# PowerOut.net
KiCad netlist of a schematic drawn in Altium Designer
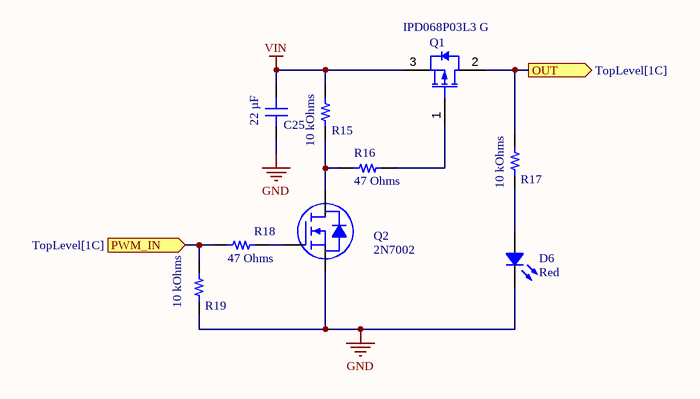
[diagram p0: PowerOut.SchDoc]

(export (version "E")
  (design (tool "Eeschema 10.0.6"))
  (components
    (comp (ref "C25")
      (value "22 µF")
      (footprint "CAP 0805_2012")
      (description "CAP0805 X5R 22UF 20% 35V")
      (fields (field (name "TOLERANCE") "±20%") (field (name "PART NUMBER") "GMC21X5R226M35NT"))
      (libsource (lib "Celestial Altium Library - altium_library") (part "Capacitor"))
    )
    (comp (ref "D6")
      (value "Red")
      (footprint "LED 0603_1608 RED")
      (description "LED RED CLEAR 0603 SMD")
      (fields
        (field (name "PART NUMBER") "LR Q976.01-P2R2-1")
        (field (name "MANUFACTURER") "ams-OSRAM USA Inc.")
      )
      (libsource (lib "Celestial Altium Library - altium_library") (part "LED"))
    )
    (comp (ref "Q1")
      (value "IPD068P03L3 G")
      (footprint "IPD068P03L3_G_0:INF-PG-TO252-3-1_M")
      (fields (field (name "MANUFACTURER") "Infineon"))
      (libsource (lib "IPD068P03L3_G") (part "IPD068P03L3 G"))
    )
    (comp (ref "Q2")
      (value "2N7002")
      (footprint "ON SEMI SOT-23-3")
      (description "MOSFET N-CH 60V 115MA SOT-23")
      (fields (field (name "MANUFACTURER") "ON Semiconductor"))
      (libsource (lib "Celestial Altium Library - altium_library") (part "ON SEMI MOSFET N-CH SOT-23-3"))
    )
    (comp (ref "R15")
      (value "10 kOhms")
      (footprint "YAGEO RES 0603_1608")
      (description "RES SMD 10K OHM 1% 1/10W 0603")
      (fields (field (name "TOLERANCE") "±1%") (field (name "PART NUMBER") "AC0603FR-0710KL"))
      (libsource (lib "Celestial Altium Library - altium_library") (part "Resistor"))
    )
    (comp (ref "R16")
      (value "47 Ohms")
      (footprint "YAGEO RES 0603_1608")
      (description "RES SMD 47 OHM 1% 1/10W 0603")
      (fields (field (name "TOLERANCE") "±1%") (field (name "PART NUMBER") "AC0603FR-0747RL"))
      (libsource (lib "Celestial Altium Library - altium_library") (part "Resistor"))
    )
    (comp (ref "R17")
      (value "10 kOhms")
      (footprint "YAGEO RES 0603_1608")
      (description "RES SMD 10K OHM 1% 1/10W 0603")
      (fields (field (name "TOLERANCE") "±1%") (field (name "PART NUMBER") "RV0603FR-0710KL"))
      (libsource (lib "Celestial Altium Library - altium_library") (part "Resistor"))
    )
    (comp (ref "R18")
      (value "47 Ohms")
      (footprint "YAGEO RES 0603_1608")
      (description "RES 47 OHM 1% 1/10W 0603")
      (fields (field (name "TOLERANCE") "±1%") (field (name "PART NUMBER") "RC0603FR-0747RL"))
      (libsource (lib "Celestial Altium Library - altium_library") (part "Resistor"))
    )
    (comp (ref "R19")
      (value "10 kOhms")
      (footprint "YAGEO RES 0603_1608")
      (description "RES SMD 10K OHM 0.25% 1/10W 0603")
      (fields (field (name "TOLERANCE") "±0.25%") (field (name "PART NUMBER") "RT0603CRE0710KL"))
      (libsource (lib "Celestial Altium Library - altium_library") (part "Resistor"))
    )
  )
  (nets
    (net (code "1") (name "/OUT") (class "Default")
      (node (ref "Q1") (pin "2") (pinfunction "DRAIN_2") (pintype "passive"))
      (node (ref "R17") (pin "1") (pinfunction "1_1") (pintype "passive"))
    )
    (net (code "2") (name "/PWM_IN") (class "Default")
      (node (ref "R18") (pin "1") (pinfunction "1_1") (pintype "passive"))
      (node (ref "R19") (pin "1") (pinfunction "1_1") (pintype "passive"))
    )
    (net (code "3") (name "GND") (class "Default")
      (node (ref "C25") (pin "2") (pinfunction "2_2") (pintype "passive"))
      (node (ref "D6") (pin "2") (pinfunction "2_2") (pintype "passive"))
      (node (ref "Q2") (pin "2") (pinfunction "S_2") (pintype "passive"))
      (node (ref "R19") (pin "2") (pinfunction "2_2") (pintype "passive"))
    )
    (net (code "4") (name "Net-(D6-Pad1)") (class "Default")
      (node (ref "D6") (pin "1") (pinfunction "1_1") (pintype "passive"))
      (node (ref "R17") (pin "2") (pinfunction "2_2") (pintype "passive"))
    )
    (net (code "5") (name "Net-(Q1-GATE)") (class "Default")
      (node (ref "Q1") (pin "1") (pinfunction "GATE_1") (pintype "passive"))
      (node (ref "R16") (pin "2") (pinfunction "2_2") (pintype "passive"))
    )
    (net (code "6") (name "Net-(Q2-D)") (class "Default")
      (node (ref "Q2") (pin "3") (pinfunction "D_3") (pintype "passive"))
      (node (ref "R15") (pin "2") (pinfunction "2_2") (pintype "passive"))
      (node (ref "R16") (pin "1") (pinfunction "1_1") (pintype "passive"))
    )
    (net (code "7") (name "Net-(Q2-G)") (class "Default")
      (node (ref "Q2") (pin "1") (pinfunction "G_1") (pintype "passive"))
      (node (ref "R18") (pin "2") (pinfunction "2_2") (pintype "passive"))
    )
    (net (code "8") (name "VIN") (class "Default")
      (node (ref "C25") (pin "1") (pinfunction "1_1") (pintype "passive"))
      (node (ref "Q1") (pin "3") (pinfunction "SOURCE_3") (pintype "passive"))
      (node (ref "R15") (pin "1") (pinfunction "1_1") (pintype "passive"))
    )
  )
)
